# discover.net
KiCad netlist of a schematic drawn in EAGLE
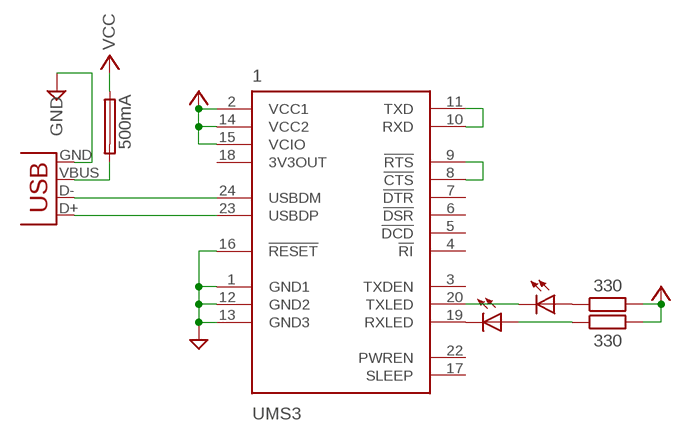
[diagram p0: schematic, sheet 1]

(export (version "E")
  (design (tool "Eeschema 10.0.6"))
  (components
    (comp (ref "1")
      (value "UMS3")
      (footprint "eagle-import:DIL-24")
      (libsource (lib "eagle-import") (part "UMS3"))
    )
    (comp (ref "F1")
      (value "500mA")
      (footprint "eagle-import:GSH15")
      (libsource (lib "eagle-import") (part "GSH15"))
    )
    (comp (ref "R1")
      (value "330")
      (footprint "eagle-import:0411_12")
      (libsource (lib "eagle-import") (part "R-EU_0411/12"))
    )
    (comp (ref "R2")
      (value "330")
      (footprint "eagle-import:0411_12")
      (libsource (lib "eagle-import") (part "R-EU_0411/12"))
    )
    (comp (ref "RLED")
      (value "LED3MM")
      (footprint "eagle-import:LED3MM")
      (libsource (lib "eagle-import") (part "LED3MM"))
    )
    (comp (ref "TLED")
      (value "LED3MM")
      (footprint "eagle-import:LED3MM")
      (libsource (lib "eagle-import") (part "LED3MM"))
    )
    (comp (ref "X1")
      (value "USB-PTH")
      (footprint "eagle-import:USB-B-PTH")
      (libsource (lib "eagle-import") (part "USB-PTH"))
    )
  )
  (nets
    (net (code "1") (name "GND") (class "Default")
      (node (ref "1") (pin "1") (pinfunction "GND1_1") (pintype "power_in"))
      (node (ref "1") (pin "12") (pinfunction "GND2_12") (pintype "power_in"))
      (node (ref "1") (pin "13") (pinfunction "GND3_13") (pintype "input"))
      (node (ref "1") (pin "16") (pinfunction "~{RESET}_16") (pintype "input"))
      (node (ref "X1") (pin "GND") (pinfunction "GND_GND") (pintype "bidirectional"))
    )
    (net (code "2") (name "Net-(1-RXD)") (class "Default")
      (node (ref "1") (pin "10") (pinfunction "RXD_10") (pintype "input"))
      (node (ref "1") (pin "11") (pinfunction "TXD_11") (pintype "output"))
    )
    (net (code "3") (name "Net-(1-RXLED)") (class "Default")
      (node (ref "1") (pin "19") (pinfunction "RXLED_19") (pintype "open_collector"))
      (node (ref "RLED") (pin "K") (pinfunction "C_K") (pintype "passive"))
    )
    (net (code "4") (name "Net-(1-TXLED)") (class "Default")
      (node (ref "1") (pin "20") (pinfunction "TXLED_20") (pintype "open_collector"))
      (node (ref "TLED") (pin "K") (pinfunction "C_K") (pintype "passive"))
    )
    (net (code "5") (name "Net-(1-USBDM)") (class "Default")
      (node (ref "1") (pin "24") (pinfunction "USBDM_24") (pintype "bidirectional"))
      (node (ref "X1") (pin "D-") (pinfunction "D-_D-") (pintype "bidirectional"))
    )
    (net (code "6") (name "Net-(1-USBDP)") (class "Default")
      (node (ref "1") (pin "23") (pinfunction "USBDP_23") (pintype "bidirectional"))
      (node (ref "X1") (pin "D+") (pinfunction "D+_D+") (pintype "bidirectional"))
    )
    (net (code "7") (name "Net-(1-~{CTS})") (class "Default")
      (node (ref "1") (pin "8") (pinfunction "~{CTS}_8") (pintype "input"))
      (node (ref "1") (pin "9") (pinfunction "~{RTS}_9") (pintype "output"))
    )
    (net (code "8") (name "Net-(F1-Pad2)") (class "Default")
      (node (ref "F1") (pin "2") (pinfunction "2_2") (pintype "passive"))
      (node (ref "X1") (pin "VBUS") (pinfunction "VBUS_VBUS") (pintype "bidirectional"))
    )
    (net (code "9") (name "Net-(R1-Pad1)") (class "Default")
      (node (ref "R1") (pin "1") (pinfunction "1_1") (pintype "passive"))
      (node (ref "RLED") (pin "A") (pinfunction "A_A") (pintype "passive"))
    )
    (net (code "10") (name "Net-(R2-Pad1)") (class "Default")
      (node (ref "R2") (pin "1") (pinfunction "1_1") (pintype "passive"))
      (node (ref "TLED") (pin "A") (pinfunction "A_A") (pintype "passive"))
    )
    (net (code "11") (name "VCC") (class "Default")
      (node (ref "1") (pin "14") (pinfunction "VCC2_14") (pintype "bidirectional"))
      (node (ref "1") (pin "15") (pinfunction "VCIO_15") (pintype "input"))
      (node (ref "1") (pin "2") (pinfunction "VCC1_2") (pintype "power_in"))
      (node (ref "F1") (pin "1") (pinfunction "1_1") (pintype "passive"))
      (node (ref "R1") (pin "2") (pinfunction "2_2") (pintype "passive"))
      (node (ref "R2") (pin "2") (pinfunction "2_2") (pintype "passive"))
    )
    (net (code "12") (name "unconnected-(1-3V3OUT-Pad18)") (class "Default")
      (node (ref "1") (pin "18") (pinfunction "3V3OUT_18") (pintype "output"))
    )
    (net (code "13") (name "unconnected-(1-PWREN-Pad22)") (class "Default")
      (node (ref "1") (pin "22") (pinfunction "PWREN_22") (pintype "output"))
    )
    (net (code "14") (name "unconnected-(1-SLEEP-Pad17)") (class "Default")
      (node (ref "1") (pin "17") (pinfunction "SLEEP_17") (pintype "output"))
    )
    (net (code "15") (name "unconnected-(1-TXDEN-Pad3)") (class "Default")
      (node (ref "1") (pin "3") (pinfunction "TXDEN_3") (pintype "output"))
    )
    (net (code "16") (name "unconnected-(1-~{DCD}-Pad5)") (class "Default")
      (node (ref "1") (pin "5") (pinfunction "~{DCD}_5") (pintype "input"))
    )
    (net (code "17") (name "unconnected-(1-~{DSR}-Pad6)") (class "Default")
      (node (ref "1") (pin "6") (pinfunction "~{DSR}_6") (pintype "input"))
    )
    (net (code "18") (name "unconnected-(1-~{DTR}-Pad7)") (class "Default")
      (node (ref "1") (pin "7") (pinfunction "~{DTR}_7") (pintype "output"))
    )
    (net (code "19") (name "unconnected-(1-~{RI}-Pad4)") (class "Default")
      (node (ref "1") (pin "4") (pinfunction "~{RI}_4") (pintype "input"))
    )
  )
)
